# Dynamixel.net
KiCad netlist of a schematic drawn in Altium Designer
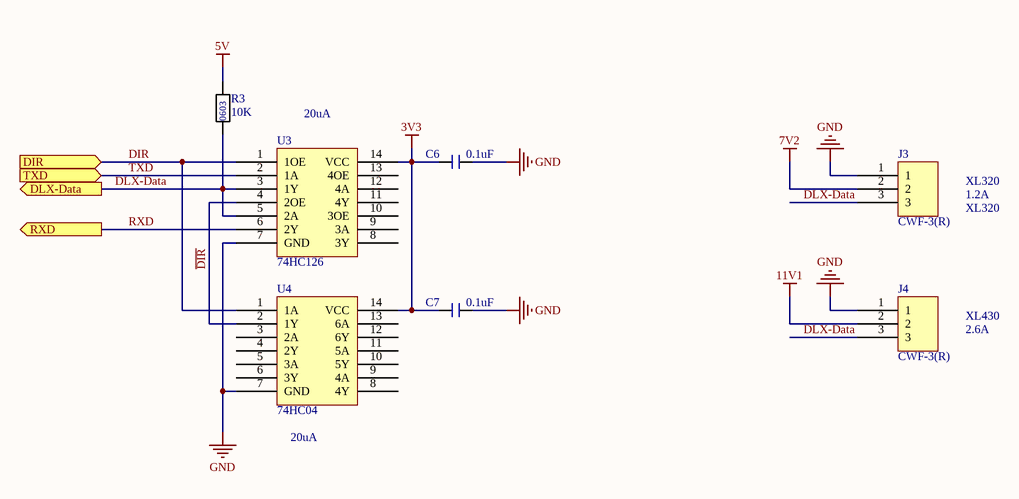
[diagram p0: Dynamixel.SchDoc]

(export (version "E")
  (design (tool "Eeschema 10.0.6"))
  (components
    (comp (ref "C6") (value "0.1uF") (footprint "CHIP_C_0603") (libsource (lib "Popular") (part "CHIP_C")))
    (comp (ref "C7") (value "0.1uF") (footprint "CHIP_C_0603") (libsource (lib "Popular") (part "CHIP_C")))
    (comp (ref "J3")
      (value "CWF-3(R)")
      (footprint "DS1066-03")
      (description "Conector")
      (libsource (lib "Popular") (part "CWF-3(R)"))
    )
    (comp (ref "J4")
      (value "CWF-3(R)")
      (footprint "CWF-3")
      (description "Conector")
      (libsource (lib "Popular") (part "CWF-3(R)"))
    )
    (comp (ref "R3") (value "10K") (footprint "CHIP_R_0603") (libsource (lib "Popular") (part "RES_0603")))
    (comp (ref "U3") (value "74HC126") (footprint "SOIC14") (libsource (lib "Popular") (part "74HC126")))
    (comp (ref "U4") (value "74HC04") (footprint "SOIC14") (libsource (lib "Popular") (part "74HC04")))
  )
  (nets
    (net (code "1") (name "/DIR") (class "Default")
      (node (ref "U3") (pin "1") (pinfunction "1OE_1") (pintype "passive"))
      (node (ref "U4") (pin "1") (pinfunction "1A_1") (pintype "passive"))
    )
    (net (code "2") (name "/DLX-Data") (class "Default")
      (node (ref "J3") (pin "3") (pinfunction "3_3") (pintype "passive"))
      (node (ref "J4") (pin "3") (pinfunction "3_3") (pintype "passive"))
      (node (ref "R3") (pin "1") (pinfunction "1_1") (pintype "passive"))
      (node (ref "U3") (pin "3") (pinfunction "1Y_3") (pintype "passive"))
      (node (ref "U3") (pin "5") (pinfunction "2A_5") (pintype "passive"))
    )
    (net (code "3") (name "/RXD") (class "Default")
      (node (ref "U3") (pin "6") (pinfunction "2Y_6") (pintype "passive"))
    )
    (net (code "4") (name "/TXD") (class "Default")
      (node (ref "U3") (pin "2") (pinfunction "1A_2") (pintype "passive"))
    )
    (net (code "5") (name "/~{DIR}") (class "Default")
      (node (ref "U3") (pin "4") (pinfunction "2OE_4") (pintype "passive"))
      (node (ref "U4") (pin "2") (pinfunction "1Y_2") (pintype "passive"))
    )
    (net (code "6") (name "3V3") (class "Default")
      (node (ref "C6") (pin "2") (pinfunction "2_2") (pintype "passive"))
      (node (ref "C7") (pin "2") (pinfunction "2_2") (pintype "passive"))
      (node (ref "U3") (pin "14") (pinfunction "VCC_14") (pintype "passive"))
      (node (ref "U4") (pin "14") (pinfunction "VCC_14") (pintype "passive"))
    )
    (net (code "7") (name "5V") (class "Default")
      (node (ref "R3") (pin "2") (pinfunction "2_2") (pintype "passive"))
    )
    (net (code "8") (name "7V2") (class "Default")
      (node (ref "J3") (pin "2") (pinfunction "2_2") (pintype "passive"))
    )
    (net (code "9") (name "11V1") (class "Default")
      (node (ref "J4") (pin "2") (pinfunction "2_2") (pintype "passive"))
    )
    (net (code "10") (name "GND") (class "Default")
      (node (ref "C6") (pin "1") (pinfunction "1_1") (pintype "passive"))
      (node (ref "C7") (pin "1") (pinfunction "1_1") (pintype "passive"))
      (node (ref "J3") (pin "1") (pinfunction "1_1") (pintype "passive"))
      (node (ref "J4") (pin "1") (pinfunction "1_1") (pintype "passive"))
      (node (ref "U3") (pin "7") (pinfunction "GND_7") (pintype "passive"))
      (node (ref "U4") (pin "7") (pinfunction "GND_7") (pintype "passive"))
    )
    (net (code "11") (name "unconnected-(U3-3A-Pad9)") (class "Default")
      (node (ref "U3") (pin "9") (pinfunction "3A_9") (pintype "passive"))
    )
    (net (code "12") (name "unconnected-(U3-3OE-Pad10)") (class "Default")
      (node (ref "U3") (pin "10") (pinfunction "3OE_10") (pintype "passive"))
    )
    (net (code "13") (name "unconnected-(U3-3Y-Pad8)") (class "Default")
      (node (ref "U3") (pin "8") (pinfunction "3Y_8") (pintype "passive"))
    )
    (net (code "14") (name "unconnected-(U3-4A-Pad12)") (class "Default")
      (node (ref "U3") (pin "12") (pinfunction "4A_12") (pintype "passive"))
    )
    (net (code "15") (name "unconnected-(U3-4OE-Pad13)") (class "Default")
      (node (ref "U3") (pin "13") (pinfunction "4OE_13") (pintype "passive"))
    )
    (net (code "16") (name "unconnected-(U3-4Y-Pad11)") (class "Default")
      (node (ref "U3") (pin "11") (pinfunction "4Y_11") (pintype "passive"))
    )
    (net (code "17") (name "unconnected-(U4-2A-Pad3)") (class "Default")
      (node (ref "U4") (pin "3") (pinfunction "2A_3") (pintype "passive"))
    )
    (net (code "18") (name "unconnected-(U4-2Y-Pad4)") (class "Default")
      (node (ref "U4") (pin "4") (pinfunction "2Y_4") (pintype "passive"))
    )
    (net (code "19") (name "unconnected-(U4-3A-Pad5)") (class "Default")
      (node (ref "U4") (pin "5") (pinfunction "3A_5") (pintype "passive"))
    )
    (net (code "20") (name "unconnected-(U4-3Y-Pad6)") (class "Default")
      (node (ref "U4") (pin "6") (pinfunction "3Y_6") (pintype "passive"))
    )
    (net (code "21") (name "unconnected-(U4-4A-Pad9)") (class "Default")
      (node (ref "U4") (pin "9") (pinfunction "4A_9") (pintype "passive"))
    )
    (net (code "22") (name "unconnected-(U4-4Y-Pad8)") (class "Default")
      (node (ref "U4") (pin "8") (pinfunction "4Y_8") (pintype "passive"))
    )
    (net (code "23") (name "unconnected-(U4-5A-Pad11)") (class "Default")
      (node (ref "U4") (pin "11") (pinfunction "5A_11") (pintype "passive"))
    )
    (net (code "24") (name "unconnected-(U4-5Y-Pad10)") (class "Default")
      (node (ref "U4") (pin "10") (pinfunction "5Y_10") (pintype "passive"))
    )
    (net (code "25") (name "unconnected-(U4-6A-Pad13)") (class "Default")
      (node (ref "U4") (pin "13") (pinfunction "6A_13") (pintype "passive"))
    )
    (net (code "26") (name "unconnected-(U4-6Y-Pad12)") (class "Default")
      (node (ref "U4") (pin "12") (pinfunction "6Y_12") (pintype "passive"))
    )
  )
)
